# LED_CONNECTOR.net
KiCad netlist of a schematic drawn in Altium Designer
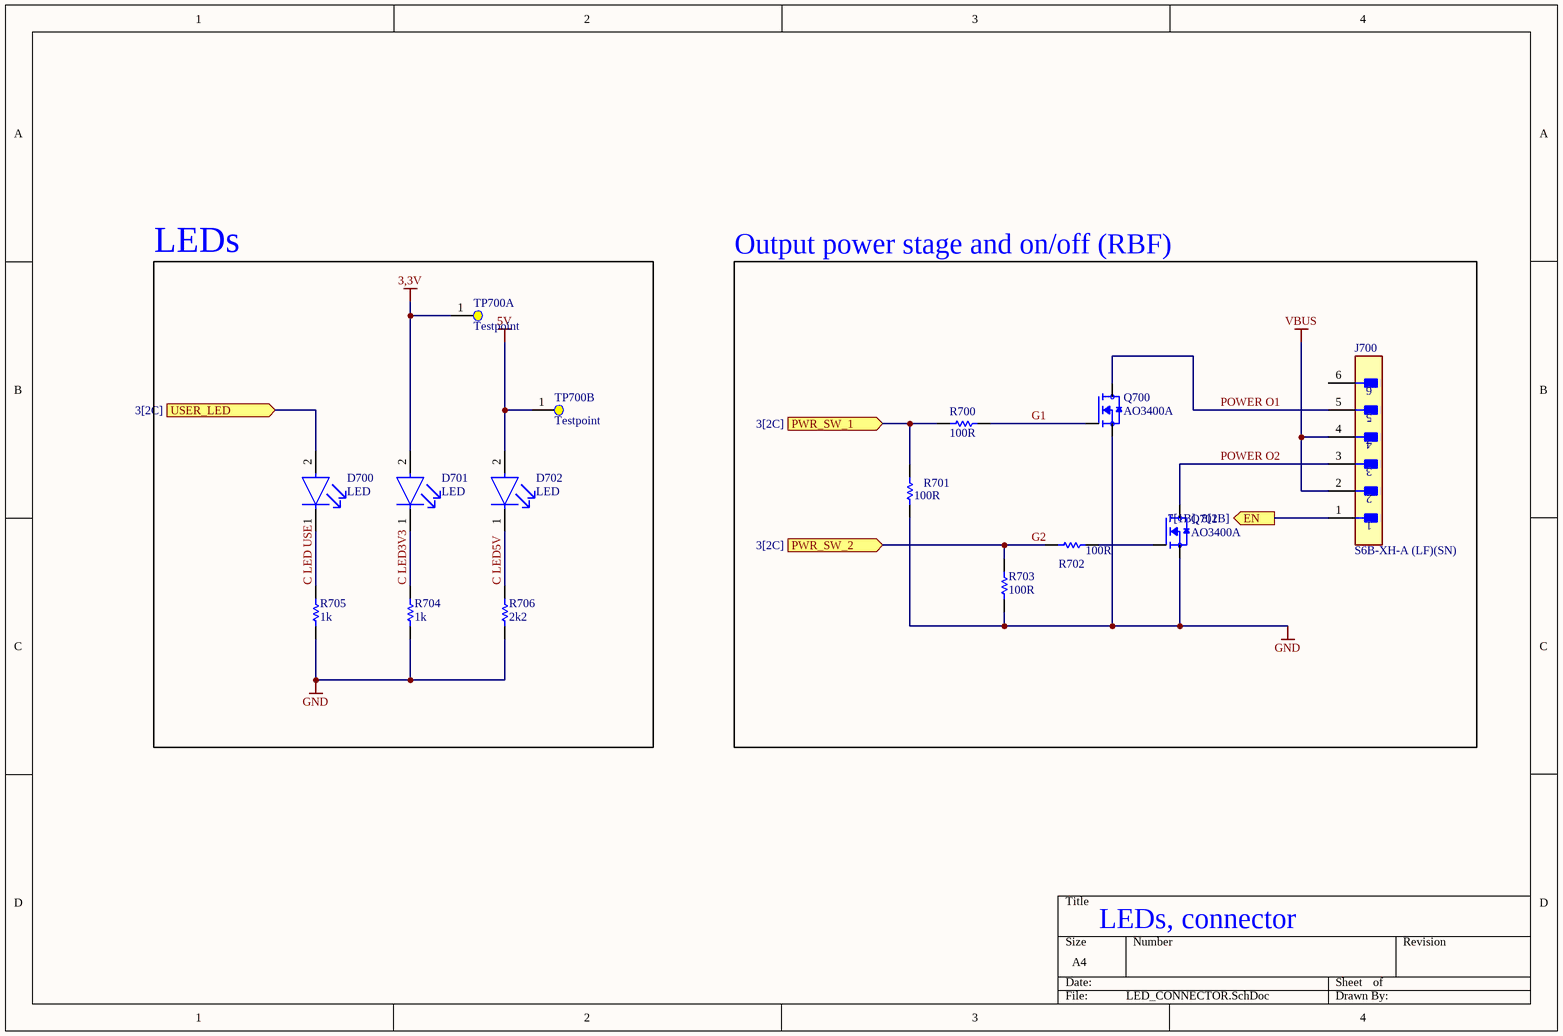
[diagram p0: LED_CONNECTOR.SchDoc]

(export (version "E")
  (design (tool "Eeschema 10.0.6"))
  (components
    (comp (ref "D700")
      (value "LED")
      (footprint "FP-HSMG-C150-MFG")
      (description "LED GREEN DIFFUSED 1206 SMD")
      (fields (field (name "MANUFACTURER PART NUMBER") "HSMG-C150") (field (name "MANUFACTURER") "Broadcom"))
      (libsource (lib "Altium Content Vault") (part "8706943c75ba83719d021d2fdc84c58"))
    )
    (comp (ref "D701")
      (value "LED")
      (footprint "FP-HSMG-C150-MFG")
      (description "LED GREEN DIFFUSED 1206 SMD")
      (fields (field (name "MANUFACTURER PART NUMBER") "HSMG-C150") (field (name "MANUFACTURER") "Broadcom"))
      (libsource (lib "Altium Content Vault") (part "8706943c75ba83719d021d2fdc84c58"))
    )
    (comp (ref "D702")
      (value "LED")
      (footprint "FP-HSMG-C150-MFG")
      (description "LED GREEN DIFFUSED 1206 SMD")
      (fields (field (name "MANUFACTURER PART NUMBER") "HSMG-C150") (field (name "MANUFACTURER") "Broadcom"))
      (libsource (lib "Altium Content Vault") (part "8706943c75ba83719d021d2fdc84c58"))
    )
    (comp (ref "J700")
      (value "S6B-XH-A (LF)(SN)")
      (footprint "FP-S6B-XH-A_LF_SN-MFG")
      (description "CONN HEADER R/A 6POS 2.5MM")
      (libsource (lib "Altium Content Vault") (part "f2cb566baf1c37ab5a3b8e90bbeafd6"))
    )
    (comp (ref "Q700")
      (value "AO3400A")
      (footprint "SOT95P280X125-3N")
      (description "Trans MOSFET N-CH 30V 5.7A 3-Pin SOT-23")
      (libsource (lib "AO3400A") (part "AO3400A"))
    )
    (comp (ref "Q701")
      (value "AO3400A")
      (footprint "SOT95P280X125-3N")
      (description "Trans MOSFET N-CH 30V 5.7A 3-Pin SOT-23")
      (libsource (lib "AO3400A") (part "AO3400A"))
    )
    (comp (ref "R700")
      (value "100R")
      (footprint "RESC1005X40X25ML05T10")
      (fields (field (name "PART NUMBER") "RC0402FR-07100RL") (field (name "MANUFACTURER") "Yageo / Phycomp"))
      (libsource (lib "Altium Content Vault") (part "RES"))
    )
    (comp (ref "R701")
      (value "100R")
      (footprint "RESC1609X50X30NL8T20")
      (description "Chip Resistor, 10 KOhm, +/- 1%, 100 mW, -55 to 155 degC, 0603 (1608 Metric), RoHS, Tape and Reel")
      (fields (field (name "MANUFACTURER") "Vishay Semiconductor"))
      (libsource (lib "Altium Content Vault") (part "RES-2"))
    )
    (comp (ref "R702")
      (value "100R")
      (footprint "RESC1005X40X25ML05T10")
      (fields (field (name "PART NUMBER") "RC0402FR-07100RL") (field (name "MANUFACTURER") "Yageo / Phycomp"))
      (libsource (lib "Altium Content Vault") (part "RES"))
    )
    (comp (ref "R703")
      (value "100R")
      (footprint "RESC1609X50X30NL8T20")
      (description "Chip Resistor, 10 KOhm, +/- 1%, 100 mW, -55 to 155 degC, 0603 (1608 Metric), RoHS, Tape and Reel")
      (fields (field (name "MANUFACTURER") "Vishay Semiconductor"))
      (libsource (lib "Altium Content Vault") (part "RES-2"))
    )
    (comp (ref "R704")
      (value "1k")
      (footprint "RESC2013X70X40LL20T20")
      (description "Chip Resistor, 1 KOhm, +/- 1%, 0.125 W, -55 to 155 degC, 0805 (2012 Metric), RoHS, Tape and Reel")
      (fields (field (name "MANUFACTURER") "Panasonic"))
      (libsource (lib "Altium Content Vault") (part "RES-2"))
    )
    (comp (ref "R705")
      (value "1k")
      (footprint "RESC2013X70X40LL20T20")
      (description "Chip Resistor, 1 KOhm, +/- 1%, 0.125 W, -55 to 155 degC, 0805 (2012 Metric), RoHS, Tape and Reel")
      (fields (field (name "MANUFACTURER") "Panasonic"))
      (libsource (lib "Altium Content Vault") (part "RES-2"))
    )
    (comp (ref "R706")
      (value "2k2")
      (footprint "RESC1609X50X30NL10T20")
      (fields (field (name "PART NUMBER") "CRCW06032K20FKEA") (field (name "MANUFACTURER") "Vishay Dale"))
      (libsource (lib "Altium Content Vault") (part "RES"))
    )
    (comp (ref "TP700A")
      (value "Testpoint")
      (footprint "Testpoint")
      (libsource (lib "SCHEMATIC") (part "Testpoint"))
    )
    (comp (ref "TP700B")
      (value "Testpoint")
      (footprint "Testpoint")
      (libsource (lib "SCHEMATIC") (part "Testpoint"))
    )
  )
  (nets
    (net (code "1") (name "/C LED USE") (class "Default")
      (node (ref "D700") (pin "1") (pinfunction "C_1") (pintype "passive"))
      (node (ref "R705") (pin "2") (pinfunction "2_2") (pintype "passive"))
    )
    (net (code "2") (name "/C LED3V3") (class "Default")
      (node (ref "D701") (pin "1") (pinfunction "C_1") (pintype "passive"))
      (node (ref "R704") (pin "2") (pinfunction "2_2") (pintype "passive"))
    )
    (net (code "3") (name "/C LED5V") (class "Default")
      (node (ref "D702") (pin "1") (pinfunction "C_1") (pintype "passive"))
      (node (ref "R706") (pin "2") (pinfunction "2_2") (pintype "passive"))
    )
    (net (code "4") (name "/EN") (class "Default")
      (node (ref "J700") (pin "1") (pinfunction "1_1") (pintype "passive"))
    )
    (net (code "5") (name "/G1") (class "Default")
      (node (ref "Q700") (pin "1") (pinfunction "G_1") (pintype "passive"))
      (node (ref "R700") (pin "2") (pinfunction "2_2") (pintype "passive"))
    )
    (net (code "6") (name "/G2") (class "Default")
      (node (ref "R702") (pin "1") (pinfunction "1_1") (pintype "passive"))
      (node (ref "R703") (pin "2") (pinfunction "2_2") (pintype "passive"))
    )
    (net (code "7") (name "/POWER O1") (class "Default")
      (node (ref "J700") (pin "5") (pinfunction "5_5") (pintype "passive"))
      (node (ref "Q700") (pin "3") (pinfunction "D_3") (pintype "passive"))
    )
    (net (code "8") (name "/POWER O2") (class "Default")
      (node (ref "J700") (pin "3") (pinfunction "3_3") (pintype "passive"))
      (node (ref "Q701") (pin "3") (pinfunction "D_3") (pintype "passive"))
    )
    (net (code "9") (name "/PWR_SW_1") (class "Default")
      (node (ref "R700") (pin "1") (pinfunction "1_1") (pintype "passive"))
      (node (ref "R701") (pin "2") (pinfunction "2_2") (pintype "passive"))
    )
    (net (code "10") (name "/USER_LED") (class "Default")
      (node (ref "D700") (pin "2") (pinfunction "A_2") (pintype "passive"))
    )
    (net (code "11") (name "3,3V") (class "Default")
      (node (ref "D701") (pin "2") (pinfunction "A_2") (pintype "passive"))
      (node (ref "TP700A") (pin "1") (pintype "passive"))
    )
    (net (code "12") (name "5V") (class "Default")
      (node (ref "D702") (pin "2") (pinfunction "A_2") (pintype "passive"))
      (node (ref "TP700B") (pin "1") (pintype "passive"))
    )
    (net (code "13") (name "GND") (class "Default")
      (node (ref "Q700") (pin "2") (pinfunction "S_2") (pintype "passive"))
      (node (ref "Q701") (pin "2") (pinfunction "S_2") (pintype "passive"))
      (node (ref "R701") (pin "1") (pinfunction "1_1") (pintype "passive"))
      (node (ref "R703") (pin "1") (pinfunction "1_1") (pintype "passive"))
      (node (ref "R704") (pin "1") (pinfunction "1_1") (pintype "passive"))
      (node (ref "R705") (pin "1") (pinfunction "1_1") (pintype "passive"))
      (node (ref "R706") (pin "1") (pinfunction "1_1") (pintype "passive"))
    )
    (net (code "14") (name "Net-(Q701-G)") (class "Default")
      (node (ref "Q701") (pin "1") (pinfunction "G_1") (pintype "passive"))
      (node (ref "R702") (pin "2") (pinfunction "2_2") (pintype "passive"))
    )
    (net (code "15") (name "VBUS") (class "Default")
      (node (ref "J700") (pin "2") (pinfunction "2_2") (pintype "passive"))
      (node (ref "J700") (pin "4") (pinfunction "4_4") (pintype "passive"))
    )
    (net (code "16") (name "unconnected-(J700-Pad6)") (class "Default")
      (node (ref "J700") (pin "6") (pinfunction "6_6") (pintype "passive"))
    )
  )
)
